# Display.net
KiCad netlist of a schematic drawn in Altium Designer
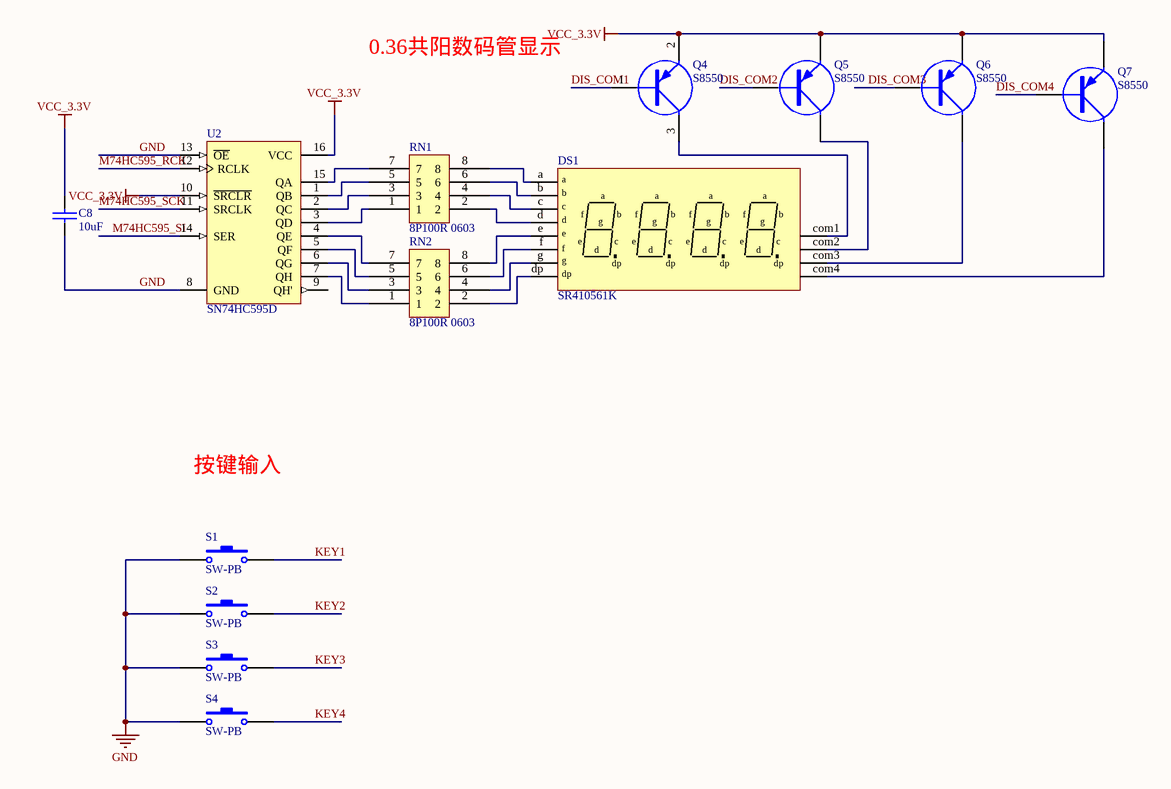
[diagram p0: Display.SchDoc]

(export (version "E")
  (design (tool "Eeschema 10.0.6"))
  (components
    (comp (ref "C8")
      (value "10uF")
      (footprint "0805c")
      (description "Capacitor")
      (libsource (lib "SM") (part "CAP"))
    )
    (comp (ref "DS1")
      (value "SR410561K")
      (footprint "SR410361")
      (description "CP-SR410561K")
      (libsource (lib "光电器件") (part "SR410561K"))
    )
    (comp (ref "Q4")
      (value "S8550")
      (footprint "SOT-23_B")
      (description "PNP Transistor")
      (libsource (lib "SM") (part "PNP"))
    )
    (comp (ref "Q5")
      (value "S8550")
      (footprint "SOT-23_B")
      (description "PNP Transistor")
      (libsource (lib "") (part "PNP_1"))
    )
    (comp (ref "Q6")
      (value "S8550")
      (footprint "SOT-23_B")
      (description "PNP Transistor")
      (libsource (lib "") (part "PNP_1"))
    )
    (comp (ref "Q7")
      (value "S8550")
      (footprint "SOT-23_B")
      (description "PNP Transistor")
      (libsource (lib "") (part "PNP_1"))
    )
    (comp (ref "RN1")
      (value "8P100R 0603")
      (footprint "8P4R_0603")
      (libsource (lib "SMD电阻") (part "8P4R 0603"))
    )
    (comp (ref "RN2")
      (value "8P100R 0603")
      (footprint "8P4R_0603")
      (libsource (lib "SMD电阻") (part "8P4R 0603"))
    )
    (comp (ref "S1")
      (value "SW-PB")
      (footprint "BUTTON_SMT_6*6")
      (description "Switch")
      (fields (field (name "PUBLISHER") "Altium Limited"))
      (libsource (lib "其他元器件") (part "SW-PB"))
    )
    (comp (ref "S2")
      (value "SW-PB")
      (footprint "BUTTON_SMT_6*6")
      (description "Switch")
      (fields (field (name "PUBLISHER") "Altium Limited"))
      (libsource (lib "其他元器件") (part "SW-PB"))
    )
    (comp (ref "S3")
      (value "SW-PB")
      (footprint "BUTTON_SMT_6*6")
      (description "Switch")
      (fields (field (name "PUBLISHER") "Altium Limited"))
      (libsource (lib "其他元器件") (part "SW-PB"))
    )
    (comp (ref "S4")
      (value "SW-PB")
      (footprint "BUTTON_SMT_6*6")
      (description "Switch")
      (fields (field (name "PUBLISHER") "Altium Limited"))
      (libsource (lib "其他元器件") (part "SW-PB"))
    )
    (comp (ref "U2")
      (value "SN74HC595D")
      (footprint "SO-16N")
      (description "8-Bit Shift Register with 3-State Output Registers")
      (fields (field (name "PUBLISHER") "Altium Limited"))
      (libsource (lib "TI Logic Register") (part "SN74HC595D"))
    )
  )
  (nets
    (net (code "1") (name "/DIS_COM1") (class "Default")
      (node (ref "Q4") (pin "1") (pinfunction "B_1") (pintype "passive"))
    )
    (net (code "2") (name "/DIS_COM2") (class "Default")
      (node (ref "Q5") (pin "1") (pinfunction "B_1") (pintype "passive"))
    )
    (net (code "3") (name "/DIS_COM3") (class "Default")
      (node (ref "Q6") (pin "1") (pinfunction "B_1") (pintype "passive"))
    )
    (net (code "4") (name "/DIS_COM4") (class "Default")
      (node (ref "Q7") (pin "1") (pinfunction "B_1") (pintype "passive"))
    )
    (net (code "5") (name "/KEY1") (class "Default")
      (node (ref "S1") (pin "2") (pinfunction "2_2") (pintype "passive"))
    )
    (net (code "6") (name "/KEY2") (class "Default")
      (node (ref "S2") (pin "2") (pinfunction "2_2") (pintype "passive"))
    )
    (net (code "7") (name "/KEY3") (class "Default")
      (node (ref "S3") (pin "2") (pinfunction "2_2") (pintype "passive"))
    )
    (net (code "8") (name "/KEY4") (class "Default")
      (node (ref "S4") (pin "2") (pinfunction "2_2") (pintype "passive"))
    )
    (net (code "9") (name "/M74HC595_RCK") (class "Default")
      (node (ref "U2") (pin "12") (pinfunction "RCLK_12") (pintype "input"))
    )
    (net (code "10") (name "/M74HC595_SCK") (class "Default")
      (node (ref "U2") (pin "11") (pinfunction "SRCLK_11") (pintype "input"))
    )
    (net (code "11") (name "/M74HC595_SI") (class "Default")
      (node (ref "U2") (pin "14") (pinfunction "SER_14") (pintype "input"))
    )
    (net (code "12") (name "GND") (class "Default")
      (node (ref "C8") (pin "1") (pinfunction "1_1") (pintype "passive"))
      (node (ref "S1") (pin "1") (pinfunction "1_1") (pintype "passive"))
      (node (ref "S2") (pin "1") (pinfunction "1_1") (pintype "passive"))
      (node (ref "S3") (pin "1") (pinfunction "1_1") (pintype "passive"))
      (node (ref "S4") (pin "1") (pinfunction "1_1") (pintype "passive"))
      (node (ref "U2") (pin "13") (pinfunction "~{OE}_13") (pintype "input"))
      (node (ref "U2") (pin "8") (pinfunction "GND_8") (pintype "power_in"))
    )
    (net (code "13") (name "Net-(DS1-Pada)") (class "Default")
      (node (ref "DS1") (pin "a") (pinfunction "a_a") (pintype "passive"))
      (node (ref "RN1") (pin "8") (pinfunction "8_8") (pintype "passive"))
    )
    (net (code "14") (name "Net-(DS1-Padb)") (class "Default")
      (node (ref "DS1") (pin "b") (pinfunction "b_b") (pintype "passive"))
      (node (ref "RN1") (pin "6") (pinfunction "6_6") (pintype "passive"))
    )
    (net (code "15") (name "Net-(DS1-Padc)") (class "Default")
      (node (ref "DS1") (pin "c") (pinfunction "c_c") (pintype "passive"))
      (node (ref "RN1") (pin "4") (pinfunction "4_4") (pintype "passive"))
    )
    (net (code "16") (name "Net-(DS1-Padd)") (class "Default")
      (node (ref "DS1") (pin "d") (pinfunction "d_d") (pintype "passive"))
      (node (ref "RN1") (pin "2") (pinfunction "2_2") (pintype "passive"))
    )
    (net (code "17") (name "Net-(DS1-Paddp)") (class "Default")
      (node (ref "DS1") (pin "dp") (pinfunction "dp_dp") (pintype "passive"))
      (node (ref "RN2") (pin "2") (pinfunction "2_2") (pintype "passive"))
    )
    (net (code "18") (name "Net-(DS1-Pade)") (class "Default")
      (node (ref "DS1") (pin "e") (pinfunction "e_e") (pintype "passive"))
      (node (ref "RN2") (pin "8") (pinfunction "8_8") (pintype "passive"))
    )
    (net (code "19") (name "Net-(DS1-Padf)") (class "Default")
      (node (ref "DS1") (pin "f") (pinfunction "f_f") (pintype "passive"))
      (node (ref "RN2") (pin "6") (pinfunction "6_6") (pintype "passive"))
    )
    (net (code "20") (name "Net-(DS1-Padg)") (class "Default")
      (node (ref "DS1") (pin "g") (pinfunction "g_g") (pintype "passive"))
      (node (ref "RN2") (pin "4") (pinfunction "4_4") (pintype "passive"))
    )
    (net (code "21") (name "Net-(Q4-C)") (class "Default")
      (node (ref "DS1") (pin "com1") (pinfunction "com1_com1") (pintype "passive"))
      (node (ref "Q4") (pin "3") (pinfunction "C_3") (pintype "passive"))
    )
    (net (code "22") (name "Net-(Q5-C)") (class "Default")
      (node (ref "DS1") (pin "com2") (pinfunction "com2_com2") (pintype "passive"))
      (node (ref "Q5") (pin "3") (pinfunction "C_3") (pintype "passive"))
    )
    (net (code "23") (name "Net-(Q6-C)") (class "Default")
      (node (ref "DS1") (pin "com3") (pinfunction "com3_com3") (pintype "passive"))
      (node (ref "Q6") (pin "3") (pinfunction "C_3") (pintype "passive"))
    )
    (net (code "24") (name "Net-(Q7-C)") (class "Default")
      (node (ref "DS1") (pin "com4") (pinfunction "com4_com4") (pintype "passive"))
      (node (ref "Q7") (pin "3") (pinfunction "C_3") (pintype "passive"))
    )
    (net (code "25") (name "Net-(U2-QA)") (class "Default")
      (node (ref "RN1") (pin "7") (pinfunction "7_7") (pintype "passive"))
      (node (ref "U2") (pin "15") (pinfunction "QA_15") (pintype "tri_state"))
    )
    (net (code "26") (name "Net-(U2-QB)") (class "Default")
      (node (ref "RN1") (pin "5") (pinfunction "5_5") (pintype "passive"))
      (node (ref "U2") (pin "1") (pinfunction "QB_1") (pintype "tri_state"))
    )
    (net (code "27") (name "Net-(U2-QC)") (class "Default")
      (node (ref "RN1") (pin "3") (pinfunction "3_3") (pintype "passive"))
      (node (ref "U2") (pin "2") (pinfunction "QC_2") (pintype "tri_state"))
    )
    (net (code "28") (name "Net-(U2-QD)") (class "Default")
      (node (ref "RN1") (pin "1") (pinfunction "1_1") (pintype "passive"))
      (node (ref "U2") (pin "3") (pinfunction "QD_3") (pintype "tri_state"))
    )
    (net (code "29") (name "Net-(U2-QE)") (class "Default")
      (node (ref "RN2") (pin "7") (pinfunction "7_7") (pintype "passive"))
      (node (ref "U2") (pin "4") (pinfunction "QE_4") (pintype "tri_state"))
    )
    (net (code "30") (name "Net-(U2-QF)") (class "Default")
      (node (ref "RN2") (pin "5") (pinfunction "5_5") (pintype "passive"))
      (node (ref "U2") (pin "5") (pinfunction "QF_5") (pintype "tri_state"))
    )
    (net (code "31") (name "Net-(U2-QG)") (class "Default")
      (node (ref "RN2") (pin "3") (pinfunction "3_3") (pintype "passive"))
      (node (ref "U2") (pin "6") (pinfunction "QG_6") (pintype "tri_state"))
    )
    (net (code "32") (name "Net-(U2-QH)") (class "Default")
      (node (ref "RN2") (pin "1") (pinfunction "1_1") (pintype "passive"))
      (node (ref "U2") (pin "7") (pinfunction "QH_7") (pintype "tri_state"))
    )
    (net (code "33") (name "VCC_3.3V") (class "Default")
      (node (ref "C8") (pin "2") (pinfunction "2_2") (pintype "passive"))
      (node (ref "Q4") (pin "2") (pinfunction "E_2") (pintype "passive"))
      (node (ref "Q5") (pin "2") (pinfunction "E_2") (pintype "passive"))
      (node (ref "Q6") (pin "2") (pinfunction "E_2") (pintype "passive"))
      (node (ref "Q7") (pin "2") (pinfunction "E_2") (pintype "passive"))
      (node (ref "U2") (pin "10") (pinfunction "~{SRCLR}_10") (pintype "input"))
      (node (ref "U2") (pin "16") (pinfunction "VCC_16") (pintype "power_in"))
    )
    (net (code "34") (name "unconnected-(U2-QH'-Pad9)") (class "Default")
      (node (ref "U2") (pin "9") (pinfunction "QH'_9") (pintype "output"))
    )
  )
)
